# SDBoard_for_CX80.net
KiCad netlist of a schematic drawn in EAGLE
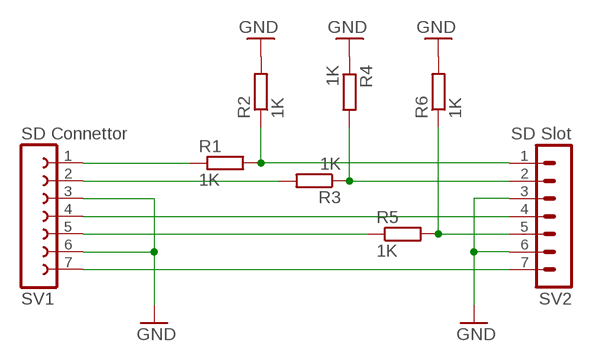
[diagram p0: schematic, sheet 1]

(export (version "E")
  (design (tool "Eeschema 10.0.6"))
  (components
    (comp (ref "R1")
      (value "1K")
      (footprint "eagle-import:0207_12")
      (libsource (lib "eagle-import") (part "R-EU_0207/12"))
    )
    (comp (ref "R2")
      (value "1K")
      (footprint "eagle-import:0207_12")
      (libsource (lib "eagle-import") (part "R-EU_0207/12"))
    )
    (comp (ref "R3")
      (value "1K")
      (footprint "eagle-import:0207_12")
      (libsource (lib "eagle-import") (part "R-EU_0207/12"))
    )
    (comp (ref "R4")
      (value "1K")
      (footprint "eagle-import:0207_12")
      (libsource (lib "eagle-import") (part "R-EU_0207/12"))
    )
    (comp (ref "R5")
      (value "1K")
      (footprint "eagle-import:0207_12")
      (libsource (lib "eagle-import") (part "R-EU_0207/12"))
    )
    (comp (ref "R6")
      (value "1K")
      (footprint "eagle-import:0207_12")
      (libsource (lib "eagle-import") (part "R-EU_0207/12"))
    )
    (comp (ref "SV1")
      (value "SD Connettor")
      (footprint "eagle-import:FE07")
      (libsource (lib "eagle-import") (part "FE07-1"))
    )
    (comp (ref "SV2")
      (value "SD Slot")
      (footprint "eagle-import:MA07-1")
      (libsource (lib "eagle-import") (part "MA07-1"))
    )
  )
  (nets
    (net (code "1") (name "GND") (class "Default")
      (node (ref "R2") (pin "2") (pinfunction "2_2") (pintype "passive"))
      (node (ref "R4") (pin "1") (pinfunction "1_1") (pintype "passive"))
      (node (ref "R6") (pin "2") (pinfunction "2_2") (pintype "passive"))
      (node (ref "SV1") (pin "3") (pinfunction "3_3") (pintype "passive"))
      (node (ref "SV1") (pin "6") (pinfunction "6_6") (pintype "passive"))
      (node (ref "SV2") (pin "3") (pinfunction "3_3") (pintype "passive"))
      (node (ref "SV2") (pin "6") (pinfunction "6_6") (pintype "passive"))
    )
    (net (code "2") (name "Net-(R1-Pad1)") (class "Default")
      (node (ref "R1") (pin "1") (pinfunction "1_1") (pintype "passive"))
      (node (ref "SV1") (pin "1") (pinfunction "1_1") (pintype "passive"))
    )
    (net (code "3") (name "Net-(R1-Pad2)") (class "Default")
      (node (ref "R1") (pin "2") (pinfunction "2_2") (pintype "passive"))
      (node (ref "R2") (pin "1") (pinfunction "1_1") (pintype "passive"))
      (node (ref "SV2") (pin "1") (pinfunction "1_1") (pintype "passive"))
    )
    (net (code "4") (name "Net-(R3-Pad1)") (class "Default")
      (node (ref "R3") (pin "1") (pinfunction "1_1") (pintype "passive"))
      (node (ref "R4") (pin "2") (pinfunction "2_2") (pintype "passive"))
      (node (ref "SV2") (pin "2") (pinfunction "2_2") (pintype "passive"))
    )
    (net (code "5") (name "Net-(R3-Pad2)") (class "Default")
      (node (ref "R3") (pin "2") (pinfunction "2_2") (pintype "passive"))
      (node (ref "SV1") (pin "2") (pinfunction "2_2") (pintype "passive"))
    )
    (net (code "6") (name "Net-(R5-Pad1)") (class "Default")
      (node (ref "R5") (pin "1") (pinfunction "1_1") (pintype "passive"))
      (node (ref "SV1") (pin "5") (pinfunction "5_5") (pintype "passive"))
    )
    (net (code "7") (name "Net-(R5-Pad2)") (class "Default")
      (node (ref "R5") (pin "2") (pinfunction "2_2") (pintype "passive"))
      (node (ref "R6") (pin "1") (pinfunction "1_1") (pintype "passive"))
      (node (ref "SV2") (pin "5") (pinfunction "5_5") (pintype "passive"))
    )
    (net (code "8") (name "Net-(SV1-Pad4)") (class "Default")
      (node (ref "SV1") (pin "4") (pinfunction "4_4") (pintype "passive"))
      (node (ref "SV2") (pin "4") (pinfunction "4_4") (pintype "passive"))
    )
    (net (code "9") (name "Net-(SV1-Pad7)") (class "Default")
      (node (ref "SV1") (pin "7") (pinfunction "7_7") (pintype "passive"))
      (node (ref "SV2") (pin "7") (pinfunction "7_7") (pintype "passive"))
    )
  )
)
